# rPiPowerHAT.net
KiCad netlist of a schematic drawn in EAGLE
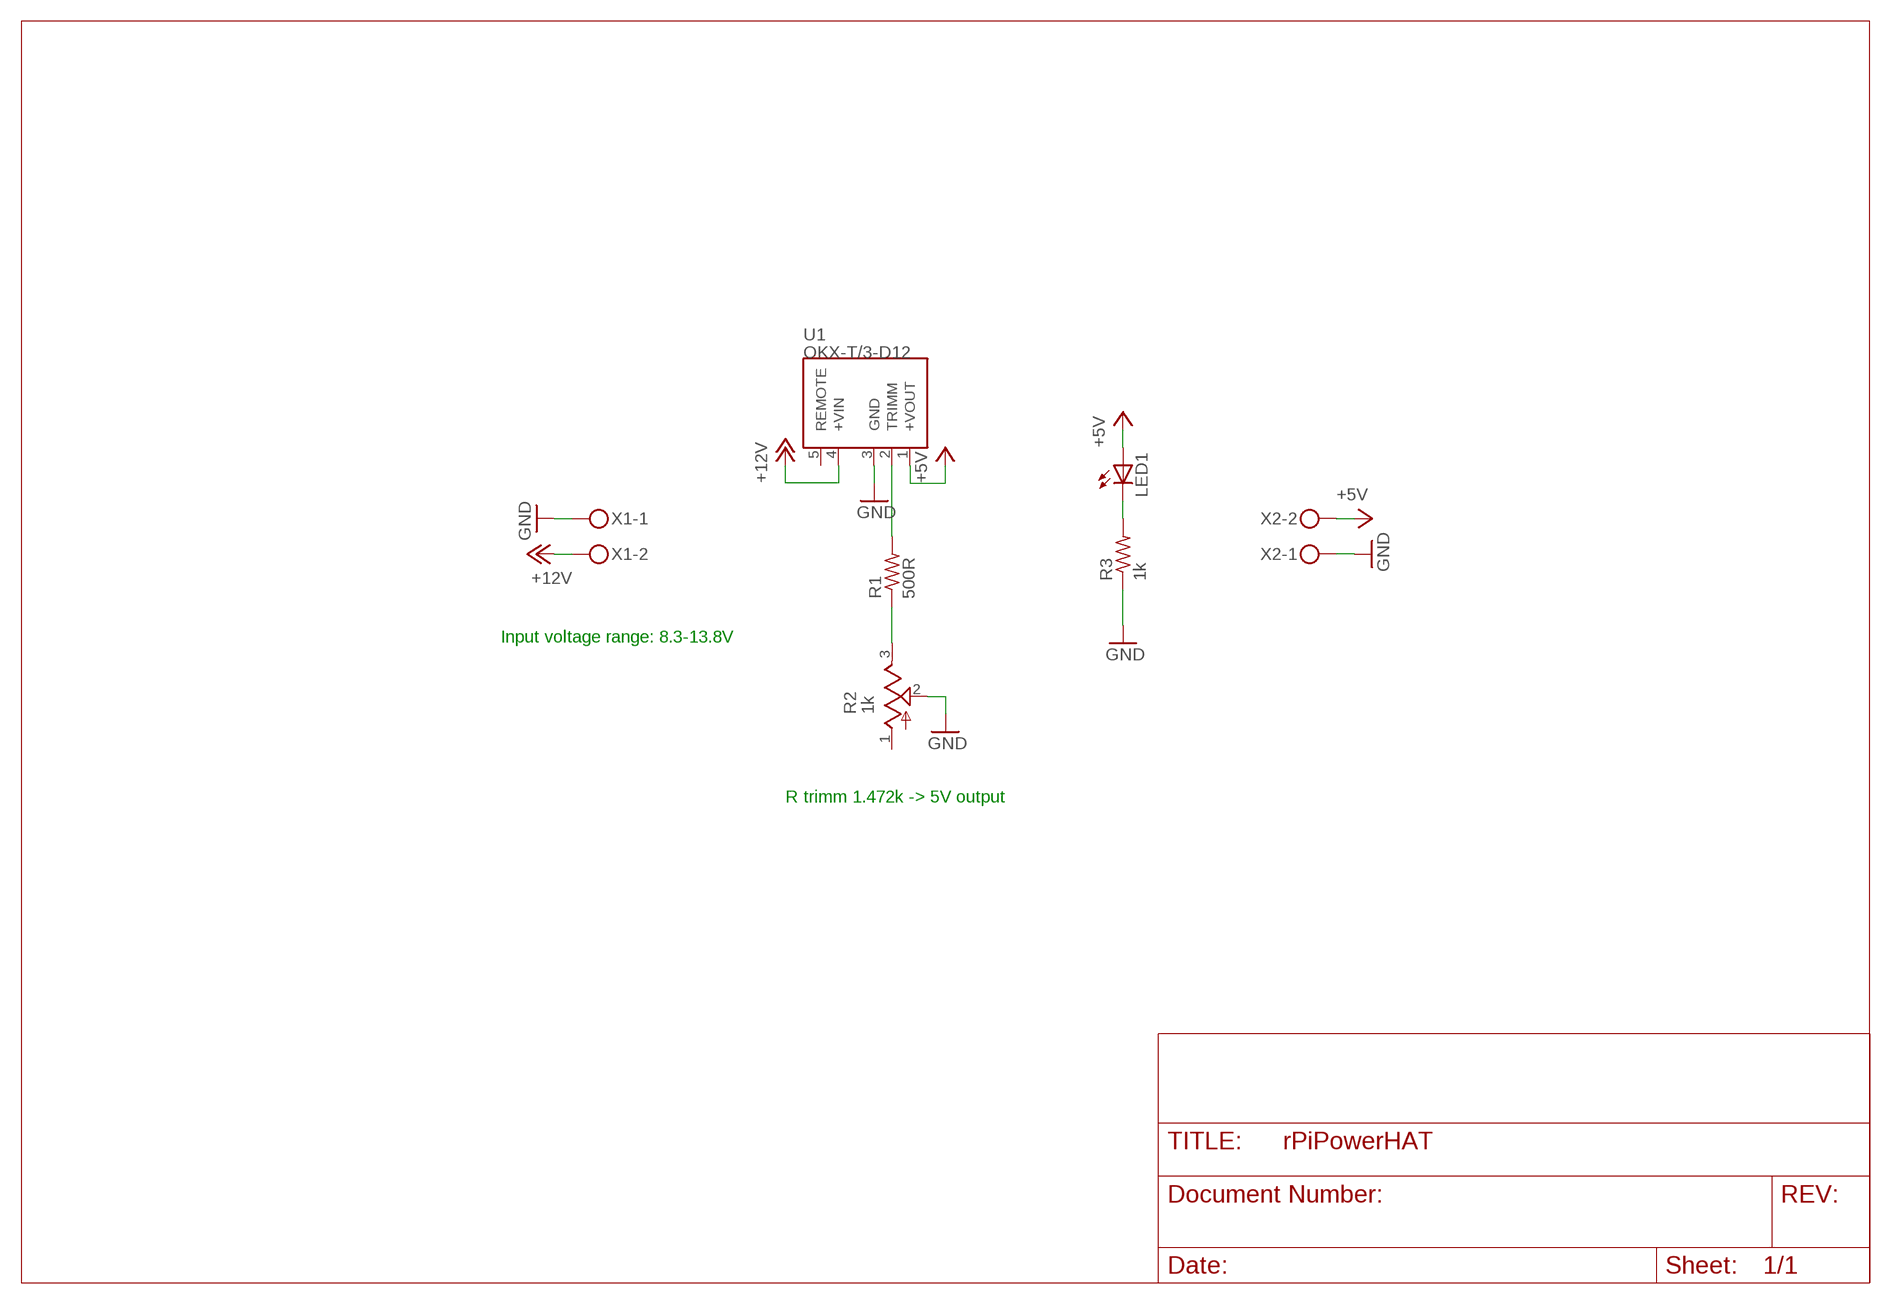
[diagram p0: schematic, sheet 1]

(export (version "E")
  (design (tool "Eeschema 10.0.6"))
  (components
    (comp (ref "LED1")
      (value "LEDCHIP-LED0603")
      (footprint "eagle-import:CHIP-LED0603")
      (libsource (lib "eagle-import") (part "LEDCHIP-LED0603"))
    )
    (comp (ref "R1")
      (value "500R")
      (footprint "eagle-import:R0603")
      (libsource (lib "eagle-import") (part "R-US_R0603"))
    )
    (comp (ref "R2")
      (value "1k")
      (footprint "eagle-import:RTRIM3296W")
      (libsource (lib "eagle-import") (part "POT-3296W"))
    )
    (comp (ref "R3")
      (value "1k")
      (footprint "eagle-import:R0603")
      (libsource (lib "eagle-import") (part "R-US_R0603"))
    )
    (comp (ref "U1")
      (value "OKX-T/3-D12")
      (footprint "eagle-import:OKX-T_3-D12")
      (libsource (lib "eagle-import") (part "OKX-T/3-D12"))
    )
    (comp (ref "X1")
      (value "MKDSN1,5/2-5,08")
      (footprint "eagle-import:MKDSN1,5_2-5,08")
      (libsource (lib "eagle-import") (part "MKDSN1,5/2-5,08"))
    )
    (comp (ref "X2")
      (value "MKDSN1,5/2-5,08")
      (footprint "eagle-import:MKDSN1,5_2-5,08")
      (libsource (lib "eagle-import") (part "MKDSN1,5/2-5,08"))
    )
  )
  (nets
    (net (code "1") (name "+5V") (class "Default")
      (node (ref "LED1") (pin "A") (pinfunction "A_A") (pintype "passive"))
      (node (ref "U1") (pin "1") (pinfunction "+VOUT_1") (pintype "bidirectional"))
      (node (ref "X2") (pin "2") (pinfunction "KL_2") (pintype "passive"))
    )
    (net (code "2") (name "+12V") (class "Default")
      (node (ref "U1") (pin "4") (pinfunction "+VIN_4") (pintype "bidirectional"))
      (node (ref "X1") (pin "2") (pinfunction "KL_2") (pintype "passive"))
    )
    (net (code "3") (name "GND") (class "Default")
      (node (ref "R2") (pin "2") (pinfunction "S_2") (pintype "passive"))
      (node (ref "R3") (pin "1") (pinfunction "1_1") (pintype "passive"))
      (node (ref "U1") (pin "3") (pinfunction "GND_3") (pintype "bidirectional"))
      (node (ref "X1") (pin "1") (pinfunction "KL_1") (pintype "passive"))
      (node (ref "X2") (pin "1") (pinfunction "KL_1") (pintype "passive"))
    )
    (net (code "4") (name "Net-(LED1-PadC)") (class "Default")
      (node (ref "LED1") (pin "C") (pinfunction "C_C") (pintype "passive"))
      (node (ref "R3") (pin "2") (pinfunction "2_2") (pintype "passive"))
    )
    (net (code "5") (name "Net-(R2-E)") (class "Default")
      (node (ref "R1") (pin "1") (pinfunction "1_1") (pintype "passive"))
      (node (ref "R2") (pin "3") (pinfunction "E_3") (pintype "passive"))
    )
    (net (code "6") (name "Net-(U1-TRIMM)") (class "Default")
      (node (ref "R1") (pin "2") (pinfunction "2_2") (pintype "passive"))
      (node (ref "U1") (pin "2") (pinfunction "TRIMM_2") (pintype "bidirectional"))
    )
    (net (code "7") (name "unconnected-(R2-A-Pad1)") (class "Default")
      (node (ref "R2") (pin "1") (pinfunction "A_1") (pintype "passive"))
    )
    (net (code "8") (name "unconnected-(U1-REMOTE-Pad5)") (class "Default")
      (node (ref "U1") (pin "5") (pinfunction "REMOTE_5") (pintype "bidirectional"))
    )
  )
)
